# ParametricMidPCB_V_1_0.net
KiCad netlist of a schematic drawn in EAGLE
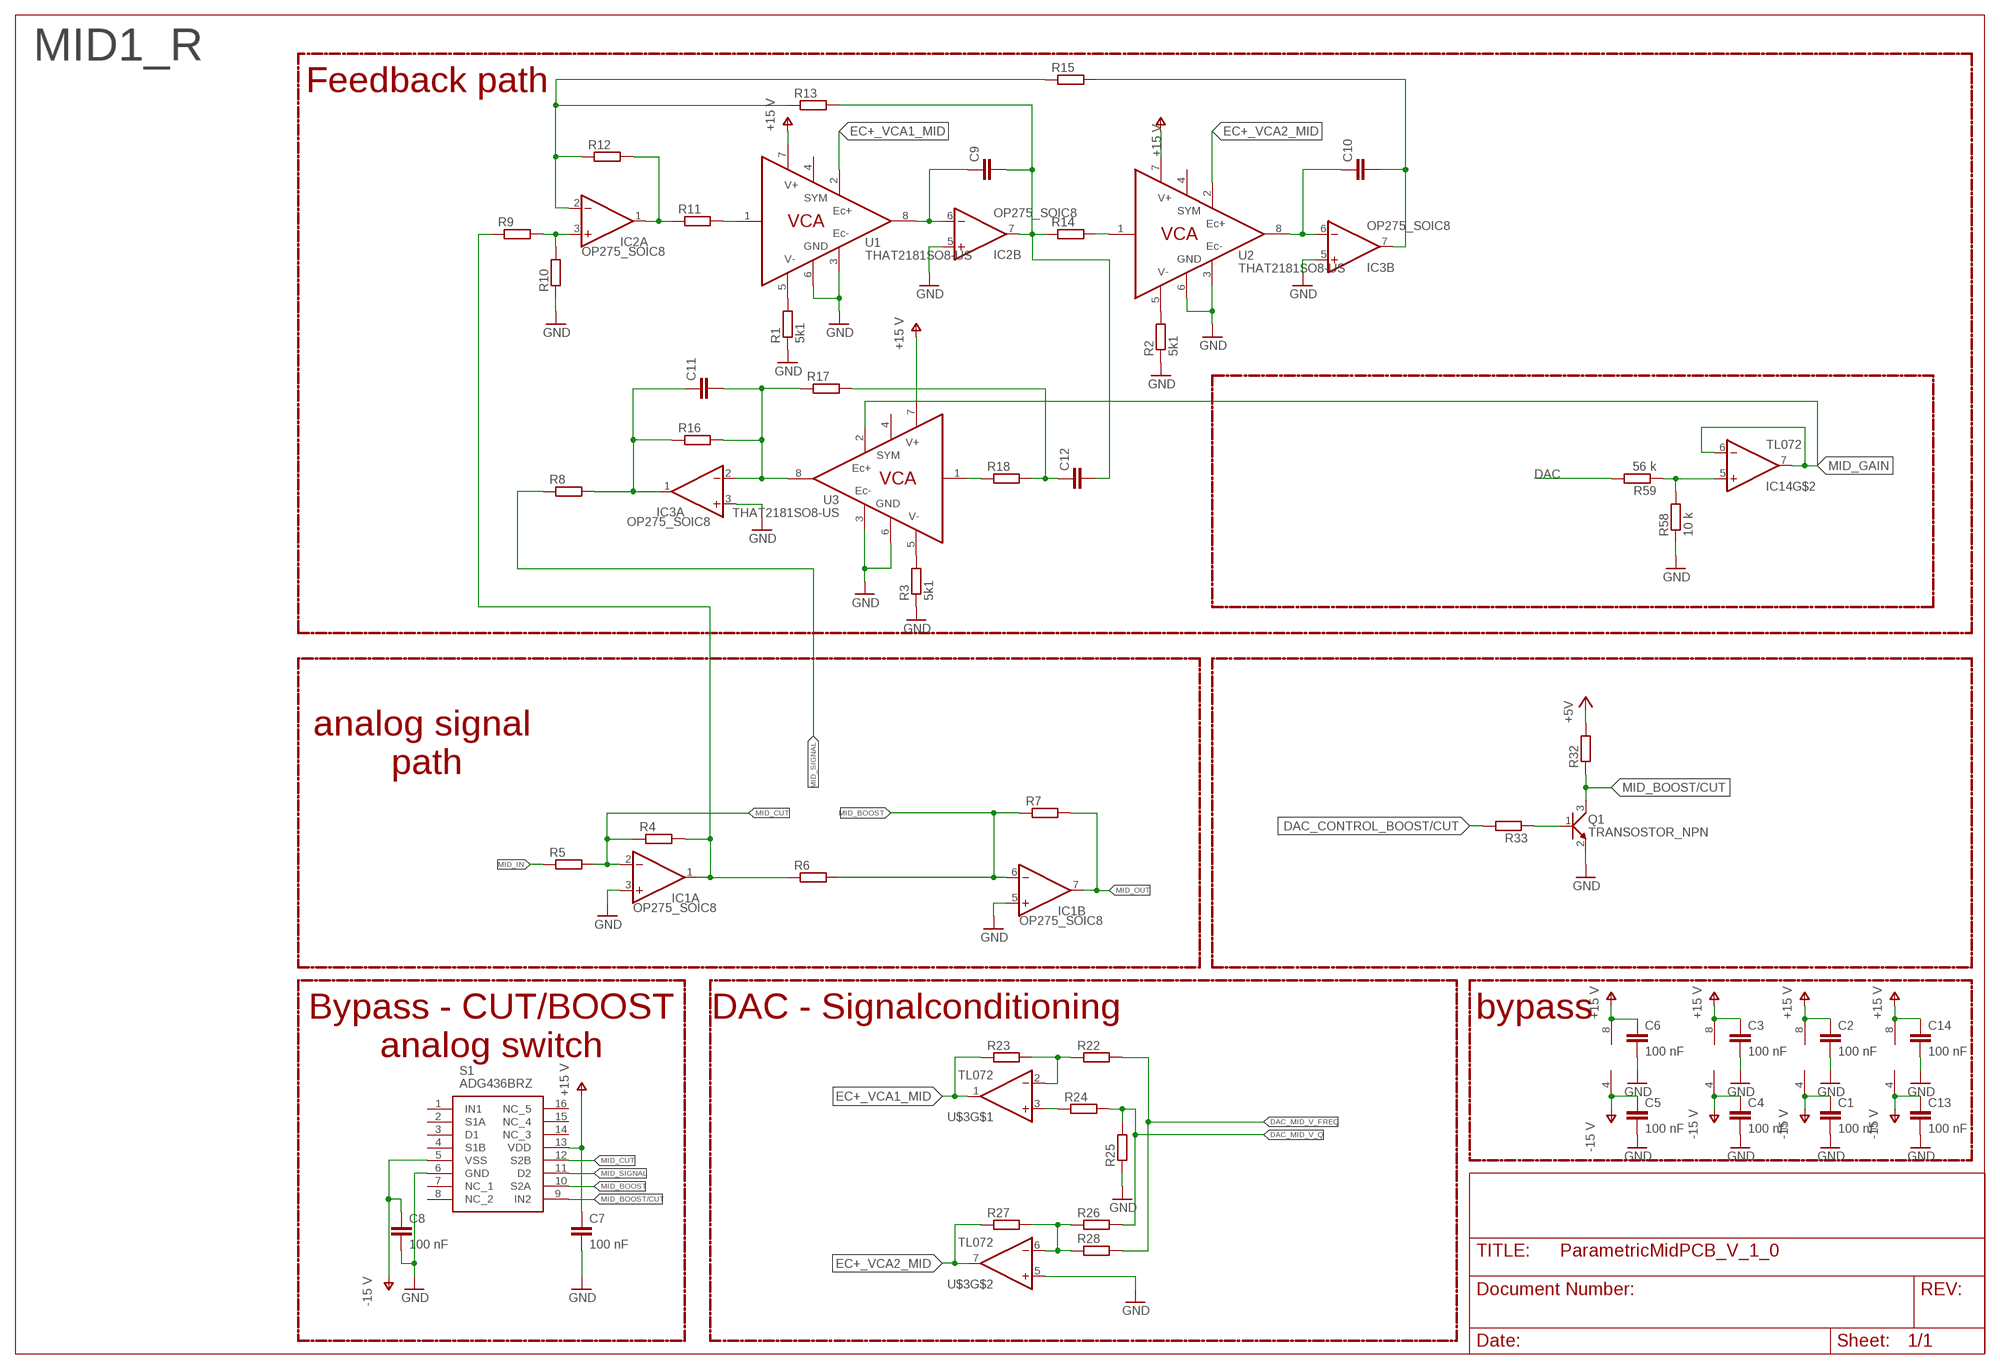
[diagram p0: schematic, sheet 1]

(export (version "E")
  (design (tool "Eeschema 10.0.6"))
  (components
    (comp (ref "C1")
      (value "100 nF")
      (footprint "eagle-import:C0603")
      (libsource (lib "eagle-import") (part "CAPACITOR_0603"))
    )
    (comp (ref "C2")
      (value "100 nF")
      (footprint "eagle-import:C0603")
      (libsource (lib "eagle-import") (part "CAPACITOR_0603"))
    )
    (comp (ref "C3")
      (value "100 nF")
      (footprint "eagle-import:C0603")
      (libsource (lib "eagle-import") (part "CAPACITOR_0603"))
    )
    (comp (ref "C4")
      (value "100 nF")
      (footprint "eagle-import:C0603")
      (libsource (lib "eagle-import") (part "CAPACITOR_0603"))
    )
    (comp (ref "C5")
      (value "100 nF")
      (footprint "eagle-import:C0603")
      (libsource (lib "eagle-import") (part "CAPACITOR_0603"))
    )
    (comp (ref "C6")
      (value "100 nF")
      (footprint "eagle-import:C0603")
      (libsource (lib "eagle-import") (part "CAPACITOR_0603"))
    )
    (comp (ref "C7")
      (value "100 nF")
      (footprint "eagle-import:C0603")
      (libsource (lib "eagle-import") (part "CAPACITOR_0603"))
    )
    (comp (ref "C8")
      (value "100 nF")
      (footprint "eagle-import:C0603")
      (libsource (lib "eagle-import") (part "CAPACITOR_0603"))
    )
    (comp (ref "C9")
      (value "CAPACITOR_0603")
      (footprint "eagle-import:C0603")
      (libsource (lib "eagle-import") (part "CAPACITOR_0603"))
    )
    (comp (ref "C10")
      (value "CAPACITOR_0603")
      (footprint "eagle-import:C0603")
      (libsource (lib "eagle-import") (part "CAPACITOR_0603"))
    )
    (comp (ref "C11")
      (value "CAPACITOR_0603")
      (footprint "eagle-import:C0603")
      (libsource (lib "eagle-import") (part "CAPACITOR_0603"))
    )
    (comp (ref "C12")
      (value "CAPACITOR_0603")
      (footprint "eagle-import:C0603")
      (libsource (lib "eagle-import") (part "CAPACITOR_0603"))
    )
    (comp (ref "C13")
      (value "100 nF")
      (footprint "eagle-import:C0603")
      (libsource (lib "eagle-import") (part "CAPACITOR_0603"))
    )
    (comp (ref "C14")
      (value "100 nF")
      (footprint "eagle-import:C0603")
      (libsource (lib "eagle-import") (part "CAPACITOR_0603"))
    )
    (comp (ref "IC1")
      (value "OP275_SOIC8")
      (footprint "eagle-import:SOIC8")
      (fields (field (name "MOUSER_PART_NUMBER") "584-OP275GSZ-R7"))
      (libsource (lib "eagle-import") (part "OP275_SOIC8"))
    )
    (comp (ref "IC2")
      (value "OP275_SOIC8")
      (footprint "eagle-import:SOIC8")
      (fields (field (name "MOUSER_PART_NUMBER") "584-OP275GSZ-R7"))
      (libsource (lib "eagle-import") (part "OP275_SOIC8"))
    )
    (comp (ref "IC3")
      (value "OP275_SOIC8")
      (footprint "eagle-import:SOIC8")
      (fields (field (name "MOUSER_PART_NUMBER") "584-OP275GSZ-R7"))
      (libsource (lib "eagle-import") (part "OP275_SOIC8"))
    )
    (comp (ref "IC14")
      (value "TL072")
      (footprint "eagle-import:SOIC8")
      (fields (field (name "MOUSER_PART_NUMBER") "595-TL072CDR"))
      (libsource (lib "eagle-import") (part "TL072"))
    )
    (comp (ref "Q1")
      (value "TRANSOSTOR_NPN")
      (footprint "eagle-import:SOT96P237X111-3N")
      (fields
        (field (name "MANUFACTURER_PART_NUMBER") "BC850CLT1G")
        (field (name "MOUSER_PART_NUMBER") "863-BC850CLT1G")
      )
      (libsource (lib "eagle-import") (part "TRANSOSTOR_NPN"))
    )
    (comp (ref "R1")
      (value "5k1")
      (footprint "eagle-import:R0603")
      (libsource (lib "eagle-import") (part "RESISTOR_0603"))
    )
    (comp (ref "R2")
      (value "5k1")
      (footprint "eagle-import:R0603")
      (libsource (lib "eagle-import") (part "RESISTOR_0603"))
    )
    (comp (ref "R3")
      (value "5k1")
      (footprint "eagle-import:R0603")
      (libsource (lib "eagle-import") (part "RESISTOR_0603"))
    )
    (comp (ref "R4")
      (value "RESISTOR_0603")
      (footprint "eagle-import:R0603")
      (libsource (lib "eagle-import") (part "RESISTOR_0603"))
    )
    (comp (ref "R5")
      (value "RESISTOR_0603")
      (footprint "eagle-import:R0603")
      (libsource (lib "eagle-import") (part "RESISTOR_0603"))
    )
    (comp (ref "R6")
      (value "RESISTOR_0603")
      (footprint "eagle-import:R0603")
      (libsource (lib "eagle-import") (part "RESISTOR_0603"))
    )
    (comp (ref "R7")
      (value "RESISTOR_0603")
      (footprint "eagle-import:R0603")
      (libsource (lib "eagle-import") (part "RESISTOR_0603"))
    )
    (comp (ref "R8")
      (value "RESISTOR_0603")
      (footprint "eagle-import:R0603")
      (libsource (lib "eagle-import") (part "RESISTOR_0603"))
    )
    (comp (ref "R9")
      (value "RESISTOR_0603")
      (footprint "eagle-import:R0603")
      (libsource (lib "eagle-import") (part "RESISTOR_0603"))
    )
    (comp (ref "R10")
      (value "RESISTOR_0603")
      (footprint "eagle-import:R0603")
      (libsource (lib "eagle-import") (part "RESISTOR_0603"))
    )
    (comp (ref "R11")
      (value "RESISTOR_0603")
      (footprint "eagle-import:R0603")
      (libsource (lib "eagle-import") (part "RESISTOR_0603"))
    )
    (comp (ref "R12")
      (value "RESISTOR_0603")
      (footprint "eagle-import:R0603")
      (libsource (lib "eagle-import") (part "RESISTOR_0603"))
    )
    (comp (ref "R13")
      (value "RESISTOR_0603")
      (footprint "eagle-import:R0603")
      (libsource (lib "eagle-import") (part "RESISTOR_0603"))
    )
    (comp (ref "R14")
      (value "RESISTOR_0603")
      (footprint "eagle-import:R0603")
      (libsource (lib "eagle-import") (part "RESISTOR_0603"))
    )
    (comp (ref "R15")
      (value "RESISTOR_0603")
      (footprint "eagle-import:R0603")
      (libsource (lib "eagle-import") (part "RESISTOR_0603"))
    )
    (comp (ref "R16")
      (value "RESISTOR_0603")
      (footprint "eagle-import:R0603")
      (libsource (lib "eagle-import") (part "RESISTOR_0603"))
    )
    (comp (ref "R17")
      (value "RESISTOR_0603")
      (footprint "eagle-import:R0603")
      (libsource (lib "eagle-import") (part "RESISTOR_0603"))
    )
    (comp (ref "R18")
      (value "RESISTOR_0603")
      (footprint "eagle-import:R0603")
      (libsource (lib "eagle-import") (part "RESISTOR_0603"))
    )
    (comp (ref "R22")
      (value "RESISTOR_0603")
      (footprint "eagle-import:R0603")
      (libsource (lib "eagle-import") (part "RESISTOR_0603"))
    )
    (comp (ref "R23")
      (value "RESISTOR_0603")
      (footprint "eagle-import:R0603")
      (libsource (lib "eagle-import") (part "RESISTOR_0603"))
    )
    (comp (ref "R24")
      (value "RESISTOR_0603")
      (footprint "eagle-import:R0603")
      (libsource (lib "eagle-import") (part "RESISTOR_0603"))
    )
    (comp (ref "R25")
      (value "RESISTOR_0603")
      (footprint "eagle-import:R0603")
      (libsource (lib "eagle-import") (part "RESISTOR_0603"))
    )
    (comp (ref "R26")
      (value "RESISTOR_0603")
      (footprint "eagle-import:R0603")
      (libsource (lib "eagle-import") (part "RESISTOR_0603"))
    )
    (comp (ref "R27")
      (value "RESISTOR_0603")
      (footprint "eagle-import:R0603")
      (libsource (lib "eagle-import") (part "RESISTOR_0603"))
    )
    (comp (ref "R28")
      (value "RESISTOR_0603")
      (footprint "eagle-import:R0603")
      (libsource (lib "eagle-import") (part "RESISTOR_0603"))
    )
    (comp (ref "R32")
      (value "RESISTOR_0603")
      (footprint "eagle-import:R0603")
      (libsource (lib "eagle-import") (part "RESISTOR_0603"))
    )
    (comp (ref "R33")
      (value "RESISTOR_0603")
      (footprint "eagle-import:R0603")
      (libsource (lib "eagle-import") (part "RESISTOR_0603"))
    )
    (comp (ref "R58")
      (value "10 k")
      (footprint "eagle-import:R0603")
      (libsource (lib "eagle-import") (part "RESISTOR_0603"))
    )
    (comp (ref "R59")
      (value "56 k")
      (footprint "eagle-import:R0603")
      (libsource (lib "eagle-import") (part "RESISTOR_0603"))
    )
    (comp (ref "S1")
      (value "ADG436BRZ")
      (footprint "eagle-import:SOIC127P600X175-16N")
      (fields (field (name "MOUSER_PART_NUMBER") "584-ADG436BRZ"))
      (libsource (lib "eagle-import") (part "ADG436BRZ"))
    )
    (comp (ref "U$3")
      (value "TL072")
      (footprint "eagle-import:SOIC8")
      (fields (field (name "MOUSER_PART_NUMBER") "595-TL072CDR"))
      (libsource (lib "eagle-import") (part "TL072"))
    )
    (comp (ref "U1")
      (value "THAT2181SO8-US")
      (footprint "eagle-import:SO08")
      (fields (field (name "MOUSER_PART_NUMBER") "887-2181CS08-U"))
      (libsource (lib "eagle-import") (part "THAT2181SSO8-U"))
    )
    (comp (ref "U2")
      (value "THAT2181SO8-US")
      (footprint "eagle-import:SO08")
      (fields (field (name "MOUSER_PART_NUMBER") "887-2181CS08-U"))
      (libsource (lib "eagle-import") (part "THAT2181SSO8-U"))
    )
    (comp (ref "U3")
      (value "THAT2181SO8-US")
      (footprint "eagle-import:SO08")
      (fields (field (name "MOUSER_PART_NUMBER") "887-2181CS08-U"))
      (libsource (lib "eagle-import") (part "THAT2181SSO8-U"))
    )
  )
  (nets
    (net (code "1") (name "+5V") (class "Default")
      (node (ref "R32") (pin "2") (pinfunction "2_2") (pintype "passive"))
    )
    (net (code "2") (name "+15 V") (class "Default")
      (node (ref "C14") (pin "1") (pinfunction "1_1") (pintype "passive"))
      (node (ref "C2") (pin "1") (pinfunction "1_1") (pintype "passive"))
      (node (ref "C3") (pin "1") (pinfunction "1_1") (pintype "passive"))
      (node (ref "C6") (pin "1") (pinfunction "1_1") (pintype "passive"))
      (node (ref "C7") (pin "1") (pinfunction "1_1") (pintype "passive"))
      (node (ref "IC1") (pin "8") (pinfunction "V+_8") (pintype "power_in"))
      (node (ref "IC2") (pin "8") (pinfunction "V+_8") (pintype "power_in"))
      (node (ref "IC3") (pin "8") (pinfunction "V+_8") (pintype "power_in"))
      (node (ref "S1") (pin "13") (pinfunction "VDD_13") (pintype "bidirectional"))
      (node (ref "U$3") (pin "8") (pinfunction "V+_8") (pintype "power_in"))
      (node (ref "U1") (pin "7") (pinfunction "V+_7") (pintype "power_in"))
      (node (ref "U2") (pin "7") (pinfunction "V+_7") (pintype "power_in"))
      (node (ref "U3") (pin "7") (pinfunction "V+_7") (pintype "power_in"))
    )
    (net (code "3") (name "-15 V") (class "Default")
      (node (ref "C1") (pin "1") (pinfunction "1_1") (pintype "passive"))
      (node (ref "C13") (pin "1") (pinfunction "1_1") (pintype "passive"))
      (node (ref "C4") (pin "1") (pinfunction "1_1") (pintype "passive"))
      (node (ref "C5") (pin "1") (pinfunction "1_1") (pintype "passive"))
      (node (ref "C8") (pin "1") (pinfunction "1_1") (pintype "passive"))
      (node (ref "IC1") (pin "4") (pinfunction "V-_4") (pintype "power_in"))
      (node (ref "IC2") (pin "4") (pinfunction "V-_4") (pintype "power_in"))
      (node (ref "IC3") (pin "4") (pinfunction "V-_4") (pintype "power_in"))
      (node (ref "S1") (pin "5") (pinfunction "VSS_5") (pintype "bidirectional"))
      (node (ref "U$3") (pin "4") (pinfunction "V-_4") (pintype "power_in"))
    )
    (net (code "4") (name "/DAC") (class "Default")
      (node (ref "R59") (pin "2") (pinfunction "2_2") (pintype "passive"))
    )
    (net (code "5") (name "DAC_CONTROL_BOOST{slash}CUT") (class "Default")
      (node (ref "R33") (pin "2") (pinfunction "2_2") (pintype "passive"))
    )
    (net (code "6") (name "DAC_MID_V_FREQ") (class "Default")
      (node (ref "R22") (pin "2") (pinfunction "2_2") (pintype "passive"))
      (node (ref "R28") (pin "2") (pinfunction "2_2") (pintype "passive"))
    )
    (net (code "7") (name "DAC_MID_V_Q") (class "Default")
      (node (ref "R24") (pin "2") (pinfunction "2_2") (pintype "passive"))
      (node (ref "R25") (pin "2") (pinfunction "2_2") (pintype "passive"))
      (node (ref "R26") (pin "2") (pinfunction "2_2") (pintype "passive"))
    )
    (net (code "8") (name "EC+_VCA1_MID") (class "Default")
      (node (ref "R23") (pin "1") (pinfunction "1_1") (pintype "passive"))
      (node (ref "U$3") (pin "1") (pinfunction "OUT_1") (pintype "output"))
      (node (ref "U1") (pin "2") (pinfunction "EC+_2") (pintype "passive"))
    )
    (net (code "9") (name "EC+_VCA2_MID") (class "Default")
      (node (ref "R27") (pin "1") (pinfunction "1_1") (pintype "passive"))
      (node (ref "U$3") (pin "7") (pinfunction "OUT_7") (pintype "output"))
      (node (ref "U2") (pin "2") (pinfunction "EC+_2") (pintype "passive"))
    )
    (net (code "10") (name "GND") (class "Default")
      (node (ref "C1") (pin "2") (pinfunction "2_2") (pintype "passive"))
      (node (ref "C13") (pin "2") (pinfunction "2_2") (pintype "passive"))
      (node (ref "C14") (pin "2") (pinfunction "2_2") (pintype "passive"))
      (node (ref "C2") (pin "2") (pinfunction "2_2") (pintype "passive"))
      (node (ref "C3") (pin "2") (pinfunction "2_2") (pintype "passive"))
      (node (ref "C4") (pin "2") (pinfunction "2_2") (pintype "passive"))
      (node (ref "C5") (pin "2") (pinfunction "2_2") (pintype "passive"))
      (node (ref "C6") (pin "2") (pinfunction "2_2") (pintype "passive"))
      (node (ref "C7") (pin "2") (pinfunction "2_2") (pintype "passive"))
      (node (ref "C8") (pin "2") (pinfunction "2_2") (pintype "passive"))
      (node (ref "IC1") (pin "3") (pinfunction "+IN_3") (pintype "input"))
      (node (ref "IC1") (pin "5") (pinfunction "+IN_5") (pintype "input"))
      (node (ref "IC2") (pin "5") (pinfunction "+IN_5") (pintype "input"))
      (node (ref "IC3") (pin "3") (pinfunction "+IN_3") (pintype "input"))
      (node (ref "IC3") (pin "5") (pinfunction "+IN_5") (pintype "input"))
      (node (ref "Q1") (pin "2") (pinfunction "E_2") (pintype "bidirectional"))
      (node (ref "R1") (pin "1") (pinfunction "1_1") (pintype "passive"))
      (node (ref "R10") (pin "1") (pinfunction "1_1") (pintype "passive"))
      (node (ref "R2") (pin "1") (pinfunction "1_1") (pintype "passive"))
      (node (ref "R25") (pin "1") (pinfunction "1_1") (pintype "passive"))
      (node (ref "R3") (pin "1") (pinfunction "1_1") (pintype "passive"))
      (node (ref "R58") (pin "1") (pinfunction "1_1") (pintype "passive"))
      (node (ref "S1") (pin "6") (pinfunction "GND_6") (pintype "bidirectional"))
      (node (ref "U$3") (pin "5") (pinfunction "+IN_5") (pintype "input"))
      (node (ref "U1") (pin "3") (pinfunction "EC-_3") (pintype "output"))
      (node (ref "U1") (pin "6") (pinfunction "GND_6") (pintype "passive"))
      (node (ref "U2") (pin "3") (pinfunction "EC-_3") (pintype "output"))
      (node (ref "U2") (pin "6") (pinfunction "GND_6") (pintype "passive"))
      (node (ref "U3") (pin "3") (pinfunction "EC-_3") (pintype "output"))
      (node (ref "U3") (pin "6") (pinfunction "GND_6") (pintype "passive"))
    )
    (net (code "11") (name "MID_BOOST") (class "Default")
      (node (ref "IC1") (pin "6") (pinfunction "-IN_6") (pintype "input"))
      (node (ref "R6") (pin "2") (pinfunction "2_2") (pintype "passive"))
      (node (ref "R7") (pin "1") (pinfunction "1_1") (pintype "passive"))
      (node (ref "S1") (pin "10") (pinfunction "S2A_10") (pintype "bidirectional"))
    )
    (net (code "12") (name "MID_BOOST{slash}CUT") (class "Default")
      (node (ref "Q1") (pin "3") (pinfunction "C_3") (pintype "bidirectional"))
      (node (ref "R32") (pin "1") (pinfunction "1_1") (pintype "passive"))
      (node (ref "S1") (pin "9") (pinfunction "IN2_9") (pintype "bidirectional"))
    )
    (net (code "13") (name "MID_CUT") (class "Default")
      (node (ref "IC1") (pin "2") (pinfunction "-IN_2") (pintype "input"))
      (node (ref "R4") (pin "1") (pinfunction "1_1") (pintype "passive"))
      (node (ref "R5") (pin "2") (pinfunction "2_2") (pintype "passive"))
      (node (ref "S1") (pin "12") (pinfunction "S2B_12") (pintype "bidirectional"))
    )
    (net (code "14") (name "MID_GAIN") (class "Default")
      (node (ref "IC14") (pin "6") (pinfunction "-IN_6") (pintype "input"))
      (node (ref "IC14") (pin "7") (pinfunction "OUT_7") (pintype "output"))
      (node (ref "U3") (pin "2") (pinfunction "EC+_2") (pintype "passive"))
    )
    (net (code "15") (name "MID_IN") (class "Default")
      (node (ref "R5") (pin "1") (pinfunction "1_1") (pintype "passive"))
    )
    (net (code "16") (name "MID_OUT") (class "Default")
      (node (ref "IC1") (pin "7") (pinfunction "OUT_7") (pintype "output"))
      (node (ref "R7") (pin "2") (pinfunction "2_2") (pintype "passive"))
    )
    (net (code "17") (name "MID_SIGNAL") (class "Default")
      (node (ref "R8") (pin "1") (pinfunction "1_1") (pintype "passive"))
      (node (ref "S1") (pin "11") (pinfunction "D2_11") (pintype "bidirectional"))
    )
    (net (code "18") (name "Net-(C12-Pad1)") (class "Default")
      (node (ref "C12") (pin "1") (pinfunction "1_1") (pintype "passive"))
      (node (ref "R17") (pin "2") (pinfunction "2_2") (pintype "passive"))
      (node (ref "R18") (pin "2") (pinfunction "2_2") (pintype "passive"))
    )
    (net (code "19") (name "Net-(IC1A-OUT)") (class "Default")
      (node (ref "IC1") (pin "1") (pinfunction "OUT_1") (pintype "output"))
      (node (ref "R4") (pin "2") (pinfunction "2_2") (pintype "passive"))
      (node (ref "R6") (pin "1") (pinfunction "1_1") (pintype "passive"))
      (node (ref "R9") (pin "1") (pinfunction "1_1") (pintype "passive"))
    )
    (net (code "20") (name "Net-(IC2A-+IN)") (class "Default")
      (node (ref "IC2") (pin "3") (pinfunction "+IN_3") (pintype "input"))
      (node (ref "R10") (pin "2") (pinfunction "2_2") (pintype "passive"))
      (node (ref "R9") (pin "2") (pinfunction "2_2") (pintype "passive"))
    )
    (net (code "21") (name "Net-(IC2A--IN)") (class "Default")
      (node (ref "IC2") (pin "2") (pinfunction "-IN_2") (pintype "input"))
      (node (ref "R12") (pin "1") (pinfunction "1_1") (pintype "passive"))
      (node (ref "R13") (pin "1") (pinfunction "1_1") (pintype "passive"))
      (node (ref "R15") (pin "1") (pinfunction "1_1") (pintype "passive"))
    )
    (net (code "22") (name "Net-(IC2A-OUT)") (class "Default")
      (node (ref "IC2") (pin "1") (pinfunction "OUT_1") (pintype "output"))
      (node (ref "R11") (pin "1") (pinfunction "1_1") (pintype "passive"))
      (node (ref "R12") (pin "2") (pinfunction "2_2") (pintype "passive"))
    )
    (net (code "23") (name "Net-(IC2B--IN)") (class "Default")
      (node (ref "C9") (pin "1") (pinfunction "1_1") (pintype "passive"))
      (node (ref "IC2") (pin "6") (pinfunction "-IN_6") (pintype "input"))
      (node (ref "U1") (pin "8") (pinfunction "OUT_8") (pintype "output"))
    )
    (net (code "24") (name "Net-(IC2B-OUT)") (class "Default")
      (node (ref "C12") (pin "2") (pinfunction "2_2") (pintype "passive"))
      (node (ref "C9") (pin "2") (pinfunction "2_2") (pintype "passive"))
      (node (ref "IC2") (pin "7") (pinfunction "OUT_7") (pintype "output"))
      (node (ref "R13") (pin "2") (pinfunction "2_2") (pintype "passive"))
      (node (ref "R14") (pin "1") (pinfunction "1_1") (pintype "passive"))
    )
    (net (code "25") (name "Net-(IC3A--IN)") (class "Default")
      (node (ref "C11") (pin "2") (pinfunction "2_2") (pintype "passive"))
      (node (ref "IC3") (pin "2") (pinfunction "-IN_2") (pintype "input"))
      (node (ref "R16") (pin "2") (pinfunction "2_2") (pintype "passive"))
      (node (ref "R17") (pin "1") (pinfunction "1_1") (pintype "passive"))
      (node (ref "U3") (pin "8") (pinfunction "OUT_8") (pintype "output"))
    )
    (net (code "26") (name "Net-(IC3A-OUT)") (class "Default")
      (node (ref "C11") (pin "1") (pinfunction "1_1") (pintype "passive"))
      (node (ref "IC3") (pin "1") (pinfunction "OUT_1") (pintype "output"))
      (node (ref "R16") (pin "1") (pinfunction "1_1") (pintype "passive"))
      (node (ref "R8") (pin "2") (pinfunction "2_2") (pintype "passive"))
    )
    (net (code "27") (name "Net-(IC3B--IN)") (class "Default")
      (node (ref "C10") (pin "1") (pinfunction "1_1") (pintype "passive"))
      (node (ref "IC3") (pin "6") (pinfunction "-IN_6") (pintype "input"))
      (node (ref "U2") (pin "8") (pinfunction "OUT_8") (pintype "output"))
    )
    (net (code "28") (name "Net-(IC3B-OUT)") (class "Default")
      (node (ref "C10") (pin "2") (pinfunction "2_2") (pintype "passive"))
      (node (ref "IC3") (pin "7") (pinfunction "OUT_7") (pintype "output"))
      (node (ref "R15") (pin "2") (pinfunction "2_2") (pintype "passive"))
    )
    (net (code "29") (name "Net-(IC14B-+IN)") (class "Default")
      (node (ref "IC14") (pin "5") (pinfunction "+IN_5") (pintype "input"))
      (node (ref "R58") (pin "2") (pinfunction "2_2") (pintype "passive"))
      (node (ref "R59") (pin "1") (pinfunction "1_1") (pintype "passive"))
    )
    (net (code "30") (name "Net-(Q1-B)") (class "Default")
      (node (ref "Q1") (pin "1") (pinfunction "B_1") (pintype "bidirectional"))
      (node (ref "R33") (pin "1") (pinfunction "1_1") (pintype "passive"))
    )
    (net (code "31") (name "Net-(U$3A-+IN)") (class "Default")
      (node (ref "R24") (pin "1") (pinfunction "1_1") (pintype "passive"))
      (node (ref "U$3") (pin "3") (pinfunction "+IN_3") (pintype "input"))
    )
    (net (code "32") (name "Net-(U$3A--IN)") (class "Default")
      (node (ref "R22") (pin "1") (pinfunction "1_1") (pintype "passive"))
      (node (ref "R23") (pin "2") (pinfunction "2_2") (pintype "passive"))
      (node (ref "U$3") (pin "2") (pinfunction "-IN_2") (pintype "input"))
    )
    (net (code "33") (name "Net-(U$3B--IN)") (class "Default")
      (node (ref "R26") (pin "1") (pinfunction "1_1") (pintype "passive"))
      (node (ref "R27") (pin "2") (pinfunction "2_2") (pintype "passive"))
      (node (ref "R28") (pin "1") (pinfunction "1_1") (pintype "passive"))
      (node (ref "U$3") (pin "6") (pinfunction "-IN_6") (pintype "input"))
    )
    (net (code "34") (name "Net-(U1-IN)") (class "Default")
      (node (ref "R11") (pin "2") (pinfunction "2_2") (pintype "passive"))
      (node (ref "U1") (pin "1") (pinfunction "IN_1") (pintype "input"))
    )
    (net (code "35") (name "Net-(U1-V-)") (class "Default")
      (node (ref "R1") (pin "2") (pinfunction "2_2") (pintype "passive"))
      (node (ref "U1") (pin "5") (pinfunction "V-_5") (pintype "power_in"))
    )
    (net (code "36") (name "Net-(U2-IN)") (class "Default")
      (node (ref "R14") (pin "2") (pinfunction "2_2") (pintype "passive"))
      (node (ref "U2") (pin "1") (pinfunction "IN_1") (pintype "input"))
    )
    (net (code "37") (name "Net-(U2-V-)") (class "Default")
      (node (ref "R2") (pin "2") (pinfunction "2_2") (pintype "passive"))
      (node (ref "U2") (pin "5") (pinfunction "V-_5") (pintype "power_in"))
    )
    (net (code "38") (name "Net-(U3-IN)") (class "Default")
      (node (ref "R18") (pin "1") (pinfunction "1_1") (pintype "passive"))
      (node (ref "U3") (pin "1") (pinfunction "IN_1") (pintype "input"))
    )
    (net (code "39") (name "Net-(U3-V-)") (class "Default")
      (node (ref "R3") (pin "2") (pinfunction "2_2") (pintype "passive"))
      (node (ref "U3") (pin "5") (pinfunction "V-_5") (pintype "power_in"))
    )
    (net (code "40") (name "unconnected-(S1-D1-Pad3)") (class "Default")
      (node (ref "S1") (pin "3") (pinfunction "D1_3") (pintype "bidirectional"))
    )
    (net (code "41") (name "unconnected-(S1-IN1-Pad1)") (class "Default")
      (node (ref "S1") (pin "1") (pinfunction "IN1_1") (pintype "bidirectional"))
    )
    (net (code "42") (name "unconnected-(S1-NC_1-Pad7)") (class "Default")
      (node (ref "S1") (pin "7") (pinfunction "NC_1_7") (pintype "bidirectional"))
    )
    (net (code "43") (name "unconnected-(S1-NC_2-Pad8)") (class "Default")
      (node (ref "S1") (pin "8") (pinfunction "NC_2_8") (pintype "bidirectional"))
    )
    (net (code "44") (name "unconnected-(S1-NC_3-Pad14)") (class "Default")
      (node (ref "S1") (pin "14") (pinfunction "NC_3_14") (pintype "bidirectional"))
    )
    (net (code "45") (name "unconnected-(S1-NC_4-Pad15)") (class "Default")
      (node (ref "S1") (pin "15") (pinfunction "NC_4_15") (pintype "bidirectional"))
    )
    (net (code "46") (name "unconnected-(S1-NC_5-Pad16)") (class "Default")
      (node (ref "S1") (pin "16") (pinfunction "NC_5_16") (pintype "bidirectional"))
    )
    (net (code "47") (name "unconnected-(S1-S1A-Pad2)") (class "Default")
      (node (ref "S1") (pin "2") (pinfunction "S1A_2") (pintype "bidirectional"))
    )
    (net (code "48") (name "unconnected-(S1-S1B-Pad4)") (class "Default")
      (node (ref "S1") (pin "4") (pinfunction "S1B_4") (pintype "bidirectional"))
    )
    (net (code "49") (name "unconnected-(U1-SYM-Pad4)") (class "Default")
      (node (ref "U1") (pin "4") (pinfunction "SYM_4") (pintype "passive"))
    )
    (net (code "50") (name "unconnected-(U2-SYM-Pad4)") (class "Default")
      (node (ref "U2") (pin "4") (pinfunction "SYM_4") (pintype "passive"))
    )
    (net (code "51") (name "unconnected-(U3-SYM-Pad4)") (class "Default")
      (node (ref "U3") (pin "4") (pinfunction "SYM_4") (pintype "passive"))
    )
  )
)
